# Servant_alternate.net
KiCad netlist of a schematic drawn in EAGLE
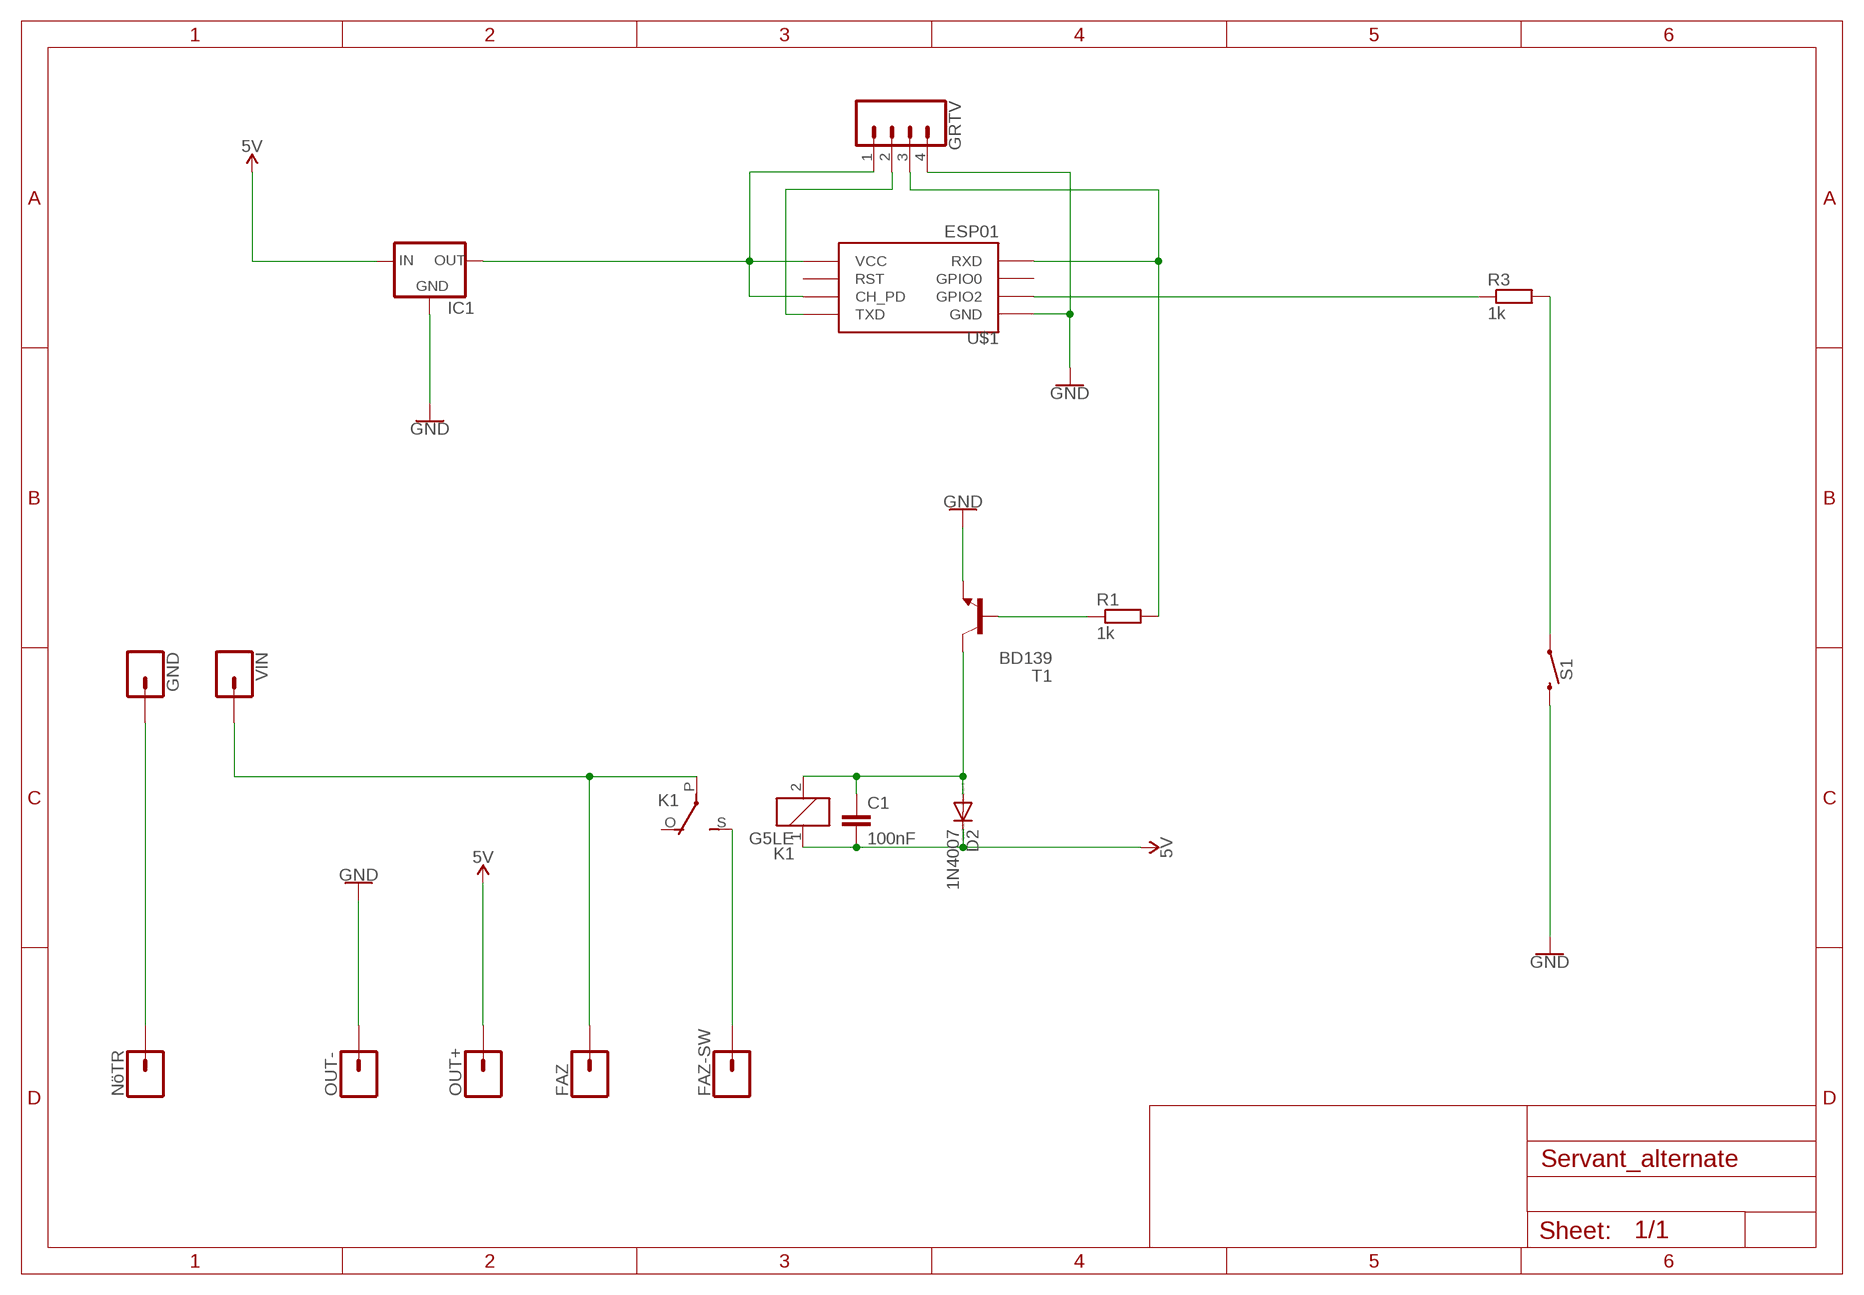
[diagram p0: schematic, sheet 1]

(export (version "E")
  (design (tool "Eeschema 10.0.6"))
  (components
    (comp (ref "C1")
      (value "100nF")
      (footprint "eagle-import:1210")
      (libsource (lib "eagle-import") (part "22UF-1210-16V-20%"))
    )
    (comp (ref "D2")
      (value "1N4007")
      (footprint "eagle-import:SMB")
      (libsource (lib "eagle-import") (part "ES2D"))
    )
    (comp (ref "FAZ")
      (value "CONN_01PTH_LONGPAD")
      (footprint "eagle-import:1X01_LONGPAD")
      (libsource (lib "eagle-import") (part "CONN_01PTH_LONGPAD"))
    )
    (comp (ref "FAZ-SW")
      (value "CONN_01PTH_LONGPAD")
      (footprint "eagle-import:1X01_LONGPAD")
      (libsource (lib "eagle-import") (part "CONN_01PTH_LONGPAD"))
    )
    (comp (ref "GND")
      (value "CONN_01")
      (footprint "eagle-import:1X01")
      (libsource (lib "eagle-import") (part "CONN_01"))
    )
    (comp (ref "GRTV")
      (value "CONN_041X04_NO_SILK")
      (footprint "eagle-import:1X04_NO_SILK")
      (libsource (lib "eagle-import") (part "CONN_041X04_NO_SILK"))
    )
    (comp (ref "IC1")
      (value "XC63FPM")
      (footprint "eagle-import:SOT23")
      (libsource (lib "eagle-import") (part "XC63FPM"))
    )
    (comp (ref "K1")
      (value "G5LE")
      (footprint "eagle-import:G5LE")
      (libsource (lib "eagle-import") (part "G5LE"))
    )
    (comp (ref "NöTR")
      (value "CONN_01PTH_LONGPAD")
      (footprint "eagle-import:1X01_LONGPAD")
      (libsource (lib "eagle-import") (part "CONN_01PTH_LONGPAD"))
    )
    (comp (ref "OUT+")
      (value "CONN_01")
      (footprint "eagle-import:1X01")
      (libsource (lib "eagle-import") (part "CONN_01"))
    )
    (comp (ref "OUT-")
      (value "CONN_01")
      (footprint "eagle-import:1X01")
      (libsource (lib "eagle-import") (part "CONN_01"))
    )
    (comp (ref "R1")
      (value "1k")
      (footprint "eagle-import:R1206")
      (libsource (lib "eagle-import") (part "R-EU_R1206"))
    )
    (comp (ref "R3")
      (value "1k")
      (footprint "eagle-import:R1206")
      (libsource (lib "eagle-import") (part "R-EU_R1206"))
    )
    (comp (ref "S1")
      (value "MOMENTARY-SWITCH-SPST-PTH-6.0MM")
      (footprint "eagle-import:TACTILE_SWITCH_PTH_6.0MM")
      (libsource (lib "eagle-import") (part "MOMENTARY-SWITCH-SPST-PTH-6.0MM"))
    )
    (comp (ref "T1")
      (value "BD139")
      (footprint "eagle-import:TO126V")
      (libsource (lib "eagle-import") (part "-NPN-TO126V"))
    )
    (comp (ref "U$1")
      (value "ESP01")
      (footprint "eagle-import:ESP01")
      (libsource (lib "eagle-import") (part "ESP01"))
    )
    (comp (ref "VIN")
      (value "CONN_01")
      (footprint "eagle-import:1X01")
      (libsource (lib "eagle-import") (part "CONN_01"))
    )
  )
  (nets
    (net (code "1") (name "5V") (class "Default")
      (node (ref "C1") (pin "2") (pinfunction "2_2") (pintype "passive"))
      (node (ref "D2") (pin "C") (pinfunction "C_C") (pintype "passive"))
      (node (ref "IC1") (pin "3") (pinfunction "IN_3") (pintype "input"))
      (node (ref "K1") (pin "1") (pinfunction "1_1") (pintype "passive"))
      (node (ref "OUT+") (pin "1") (pinfunction "1_1") (pintype "passive"))
    )
    (net (code "2") (name "GND") (class "Default")
      (node (ref "GRTV") (pin "4") (pinfunction "4_4") (pintype "passive"))
      (node (ref "IC1") (pin "1") (pinfunction "GND_1") (pintype "input"))
      (node (ref "OUT-") (pin "1") (pinfunction "1_1") (pintype "passive"))
      (node (ref "S1") (pin "3") (pinfunction "2_3") (pintype "passive"))
      (node (ref "T1") (pin "1") (pinfunction "E_1") (pintype "passive"))
      (node (ref "U$1") (pin "GND") (pinfunction "GND_GND") (pintype "bidirectional"))
    )
    (net (code "3") (name "Net-(FAZ-Pad1)") (class "Default")
      (node (ref "FAZ") (pin "1") (pinfunction "1_1") (pintype "passive"))
      (node (ref "K1") (pin "P") (pinfunction "P_P") (pintype "passive"))
      (node (ref "VIN") (pin "1") (pinfunction "1_1") (pintype "passive"))
    )
    (net (code "4") (name "Net-(FAZ-SW-Pad1)") (class "Default")
      (node (ref "FAZ-SW") (pin "1") (pinfunction "1_1") (pintype "passive"))
      (node (ref "K1") (pin "S") (pinfunction "S_S") (pintype "passive"))
    )
    (net (code "5") (name "Net-(GND-Pad1)") (class "Default")
      (node (ref "GND") (pin "1") (pinfunction "1_1") (pintype "passive"))
      (node (ref "NöTR") (pin "1") (pinfunction "1_1") (pintype "passive"))
    )
    (net (code "6") (name "Net-(IC1-OUT)") (class "Default")
      (node (ref "GRTV") (pin "1") (pinfunction "1_1") (pintype "passive"))
      (node (ref "IC1") (pin "2") (pinfunction "OUT_2") (pintype "passive"))
      (node (ref "U$1") (pin "CH_PD") (pinfunction "CH_PD_CH_PD") (pintype "bidirectional"))
      (node (ref "U$1") (pin "VCC") (pinfunction "VCC_VCC") (pintype "bidirectional"))
    )
    (net (code "7") (name "Net-(R3-Pad1)") (class "Default")
      (node (ref "R3") (pin "1") (pinfunction "1_1") (pintype "passive"))
      (node (ref "U$1") (pin "GPIO2") (pinfunction "GPIO2_GPIO2") (pintype "bidirectional"))
    )
    (net (code "8") (name "Net-(R3-Pad2)") (class "Default")
      (node (ref "R3") (pin "2") (pinfunction "2_2") (pintype "passive"))
      (node (ref "S1") (pin "1") (pinfunction "1_1") (pintype "passive"))
    )
    (net (code "9") (name "Net-(T1-B)") (class "Default")
      (node (ref "R1") (pin "1") (pinfunction "1_1") (pintype "passive"))
      (node (ref "T1") (pin "3") (pinfunction "B_3") (pintype "passive"))
    )
    (net (code "10") (name "Net-(T1-C)") (class "Default")
      (node (ref "C1") (pin "1") (pinfunction "1_1") (pintype "passive"))
      (node (ref "D2") (pin "A") (pinfunction "A_A") (pintype "passive"))
      (node (ref "K1") (pin "2") (pinfunction "2_2") (pintype "passive"))
      (node (ref "T1") (pin "2") (pinfunction "C_2") (pintype "passive"))
    )
    (net (code "11") (name "Net-(U$1-RXD)") (class "Default")
      (node (ref "GRTV") (pin "3") (pinfunction "3_3") (pintype "passive"))
      (node (ref "R1") (pin "2") (pinfunction "2_2") (pintype "passive"))
      (node (ref "U$1") (pin "RX") (pinfunction "RXD_RX") (pintype "bidirectional"))
    )
    (net (code "12") (name "Net-(U$1-TXD)") (class "Default")
      (node (ref "GRTV") (pin "2") (pinfunction "2_2") (pintype "passive"))
      (node (ref "U$1") (pin "TX") (pinfunction "TXD_TX") (pintype "bidirectional"))
    )
    (net (code "13") (name "unconnected-(K1-PadO)") (class "Default")
      (node (ref "K1") (pin "O") (pinfunction "O_O") (pintype "passive"))
    )
    (net (code "14") (name "unconnected-(U$1-PadGPIO0)") (class "Default")
      (node (ref "U$1") (pin "GPIO0") (pinfunction "GPIO0_GPIO0") (pintype "bidirectional"))
    )
    (net (code "15") (name "unconnected-(U$1-PadRST)") (class "Default")
      (node (ref "U$1") (pin "RST") (pinfunction "RST_RST") (pintype "bidirectional"))
    )
  )
)
